# LAUNCHXL-F28377S_4.net
KiCad netlist of a schematic drawn in Altium Designer
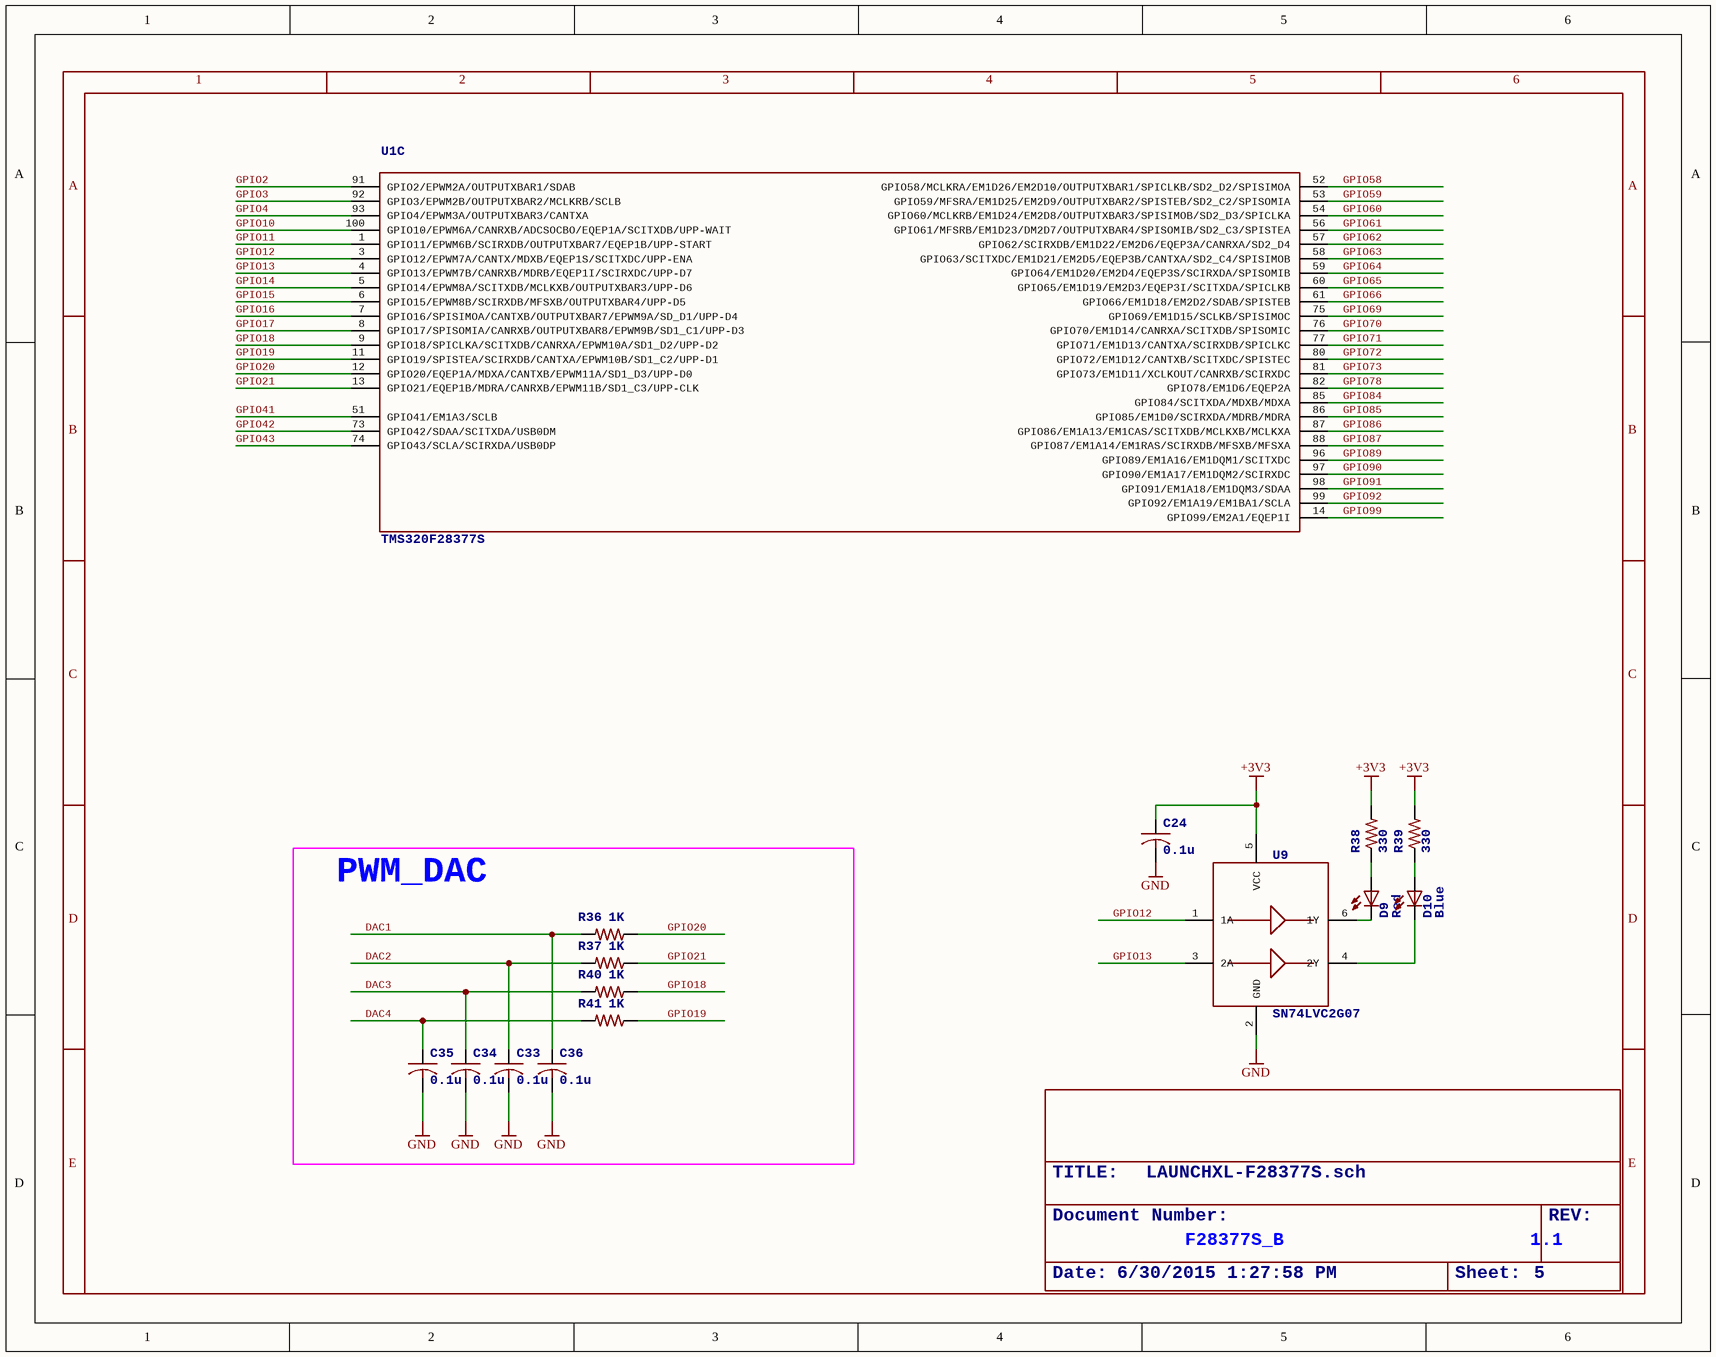
[diagram p0: LAUNCHXL-F28377S_4.SchDoc]

(export (version "E")
  (design (tool "Eeschema 10.0.6"))
  (components
    (comp (ref "C24")
      (value "0.1u")
      (footprint "C0402")
      (description "<B>CAPACITOR</B>, American symbol")
      (libsource (lib "rcl") (part "C-USC0402"))
    )
    (comp (ref "C33")
      (value "0.1u")
      (footprint "C0402")
      (description "<B>CAPACITOR</B>, American symbol")
      (libsource (lib "rcl") (part "C-USC0402"))
    )
    (comp (ref "C34")
      (value "0.1u")
      (footprint "C0402")
      (description "<B>CAPACITOR</B>, American symbol")
      (libsource (lib "rcl") (part "C-USC0402"))
    )
    (comp (ref "C35")
      (value "0.1u")
      (footprint "C0402")
      (description "<B>CAPACITOR</B>, American symbol")
      (libsource (lib "rcl") (part "C-USC0402"))
    )
    (comp (ref "C36")
      (value "0.1u")
      (footprint "C0402")
      (description "<B>CAPACITOR</B>, American symbol")
      (libsource (lib "rcl") (part "C-USC0402"))
    )
    (comp (ref "D9")
      (value "Red")
      (footprint "CHIP-LED0603")
      (libsource (lib "led") (part "LEDCHIP-LED0603"))
    )
    (comp (ref "D10")
      (value "Blue")
      (footprint "CHIP-LED0603")
      (libsource (lib "led") (part "LEDCHIP-LED0603"))
    )
    (comp (ref "R36")
      (value "1K")
      (footprint "R0402")
      (description "<B>RESISTOR</B>, American symbol")
      (libsource (lib "rcl") (part "R-US_R0402"))
    )
    (comp (ref "R37")
      (value "1K")
      (footprint "R0402")
      (description "<B>RESISTOR</B>, American symbol")
      (libsource (lib "rcl") (part "R-US_R0402"))
    )
    (comp (ref "R38")
      (value "330")
      (footprint "R0402")
      (description "<B>RESISTOR</B>, American symbol")
      (libsource (lib "rcl") (part "R-US_R0402"))
    )
    (comp (ref "R39")
      (value "330")
      (footprint "R0402")
      (description "<B>RESISTOR</B>, American symbol")
      (libsource (lib "rcl") (part "R-US_R0402"))
    )
    (comp (ref "R40")
      (value "1K")
      (footprint "R0402")
      (description "<B>RESISTOR</B>, American symbol")
      (libsource (lib "rcl") (part "R-US_R0402"))
    )
    (comp (ref "R41")
      (value "1K")
      (footprint "R0402")
      (description "<B>RESISTOR</B>, American symbol")
      (libsource (lib "rcl") (part "R-US_R0402"))
    )
    (comp (ref "U1")
      (value "TMS320F28377S")
      (footprint "PQFP100_THERMAL")
      (libsource (lib "LAUNCHXL-F28377S") (part "TMS320F28377S"))
    )
    (comp (ref "U9")
      (value "SN74LVC2G07")
      (footprint "SOT23-6-DBV")
      (libsource (lib "texas") (part "SN74LVC2G07"))
    )
  )
  (nets
    (net (code "1") (name "+3V3") (class "Default")
      (node (ref "C24") (pin "1") (pinfunction "1_1") (pintype "passive"))
      (node (ref "R38") (pin "2") (pinfunction "2_2") (pintype "passive"))
      (node (ref "R39") (pin "2") (pinfunction "2_2") (pintype "passive"))
      (node (ref "U9") (pin "5") (pinfunction "VCC_5") (pintype "passive"))
    )
    (net (code "2") (name "/DAC1") (class "Default")
      (node (ref "C36") (pin "1") (pinfunction "1_1") (pintype "passive"))
      (node (ref "R36") (pin "2") (pinfunction "2_2") (pintype "passive"))
    )
    (net (code "3") (name "/DAC2") (class "Default")
      (node (ref "C33") (pin "1") (pinfunction "1_1") (pintype "passive"))
      (node (ref "R37") (pin "2") (pinfunction "2_2") (pintype "passive"))
    )
    (net (code "4") (name "/DAC3") (class "Default")
      (node (ref "C34") (pin "1") (pinfunction "1_1") (pintype "passive"))
      (node (ref "R40") (pin "2") (pinfunction "2_2") (pintype "passive"))
    )
    (net (code "5") (name "/DAC4") (class "Default")
      (node (ref "C35") (pin "1") (pinfunction "1_1") (pintype "passive"))
      (node (ref "R41") (pin "2") (pinfunction "2_2") (pintype "passive"))
    )
    (net (code "6") (name "/GPIO2") (class "Default")
      (node (ref "U1") (pin "91") (pinfunction "GPIO2/EPWM2A/OUTPUTXBAR1/SDAB_91") (pintype "passive"))
    )
    (net (code "7") (name "/GPIO3") (class "Default")
      (node (ref "U1") (pin "92") (pinfunction "GPIO3/EPWM2B/OUTPUTXBAR2/MCLKRB/SCLB_92") (pintype "passive"))
    )
    (net (code "8") (name "/GPIO4") (class "Default")
      (node (ref "U1") (pin "93") (pinfunction "GPIO4/EPWM3A/OUTPUTXBAR3/CANTXA_93") (pintype "passive"))
    )
    (net (code "9") (name "/GPIO10") (class "Default")
      (node (ref "U1") (pin "100") (pinfunction "GPIO10/EPWM6A/CANRXB/ADCSOCBO/EQEP1A/SCITXDB/UPP-WAIT_100") (pintype "passive"))
    )
    (net (code "10") (name "/GPIO11") (class "Default")
      (node (ref "U1") (pin "1") (pinfunction "GPIO11/EPWM6B/SCIRXDB/OUTPUTXBAR7/EQEP1B/UPP-START_1") (pintype "passive"))
    )
    (net (code "11") (name "/GPIO12") (class "Default")
      (node (ref "U1") (pin "3") (pinfunction "GPIO12/EPWM7A/CANTX/MDXB/EQEP1S/SCITXDC/UPP-ENA_3") (pintype "passive"))
      (node (ref "U9") (pin "1") (pinfunction "1A_1") (pintype "passive"))
    )
    (net (code "12") (name "/GPIO13") (class "Default")
      (node (ref "U1") (pin "4") (pinfunction "GPIO13/EPWM7B/CANRXB/MDRB/EQEP1I/SCIRXDC/UPP-D7_4") (pintype "passive"))
      (node (ref "U9") (pin "3") (pinfunction "2A_3") (pintype "passive"))
    )
    (net (code "13") (name "/GPIO14") (class "Default")
      (node (ref "U1") (pin "5") (pinfunction "GPIO14/EPWM8A/SCITXDB/MCLKXB/OUTPUTXBAR3/UPP-D6_5") (pintype "passive"))
    )
    (net (code "14") (name "/GPIO15") (class "Default")
      (node (ref "U1") (pin "6") (pinfunction "GPIO15/EPWM8B/SCIRXDB/MFSXB/OUTPUTXBAR4/UPP-D5_6") (pintype "passive"))
    )
    (net (code "15") (name "/GPIO16") (class "Default")
      (node (ref "U1") (pin "7") (pinfunction "GPIO16/SPISIMOA/CANTXB/OUTPUTXBAR7/EPWM9A/SD_D1/UPP-D4_7") (pintype "passive"))
    )
    (net (code "16") (name "/GPIO17") (class "Default")
      (node (ref "U1") (pin "8") (pinfunction "GPIO17/SPISOMIA/CANRXB/OUTPUTXBAR8/EPWM9B/SD1_C1/UPP-D3_8") (pintype "passive"))
    )
    (net (code "17") (name "/GPIO18") (class "Default")
      (node (ref "R40") (pin "1") (pinfunction "1_1") (pintype "passive"))
      (node (ref "U1") (pin "9") (pinfunction "GPIO18/SPICLKA/SCITXDB/CANRXA/EPWM10A/SD1_D2/UPP-D2_9") (pintype "passive"))
    )
    (net (code "18") (name "/GPIO19") (class "Default")
      (node (ref "R41") (pin "1") (pinfunction "1_1") (pintype "passive"))
      (node (ref "U1") (pin "11") (pinfunction "GPIO19/SPISTEA/SCIRXDB/CANTXA/EPWM10B/SD1_C2/UPP-D1_11") (pintype "passive"))
    )
    (net (code "19") (name "/GPIO20") (class "Default")
      (node (ref "R36") (pin "1") (pinfunction "1_1") (pintype "passive"))
      (node (ref "U1") (pin "12") (pinfunction "GPIO20/EQEP1A/MDXA/CANTXB/EPWM11A/SD1_D3/UPP-D0_12") (pintype "passive"))
    )
    (net (code "20") (name "/GPIO21") (class "Default")
      (node (ref "R37") (pin "1") (pinfunction "1_1") (pintype "passive"))
      (node (ref "U1") (pin "13") (pinfunction "GPIO21/EQEP1B/MDRA/CANRXB/EPWM11B/SD1_C3/UPP-CLK_13") (pintype "passive"))
    )
    (net (code "21") (name "/GPIO41") (class "Default")
      (node (ref "U1") (pin "51") (pinfunction "GPIO41/EM1A3/SCLB_51") (pintype "passive"))
    )
    (net (code "22") (name "/GPIO42") (class "Default")
      (node (ref "U1") (pin "73") (pinfunction "GPIO42/SDAA/SCITXDA/USB0DM_73") (pintype "passive"))
    )
    (net (code "23") (name "/GPIO43") (class "Default")
      (node (ref "U1") (pin "74") (pinfunction "GPIO43/SCLA/SCIRXDA/USB0DP_74") (pintype "passive"))
    )
    (net (code "24") (name "/GPIO58") (class "Default")
      (node (ref "U1") (pin "52") (pinfunction "GPIO58/MCLKRA/EM1D26/EM2D10/OUTPUTXBAR1/SPICLKB/SD2_D2/SPISIMOA_52") (pintype "passive"))
    )
    (net (code "25") (name "/GPIO59") (class "Default")
      (node (ref "U1") (pin "53") (pinfunction "GPIO59/MFSRA/EM1D25/EM2D9/OUTPUTXBAR2/SPISTEB/SD2_C2/SPISOMIA_53") (pintype "passive"))
    )
    (net (code "26") (name "/GPIO60") (class "Default")
      (node (ref "U1") (pin "54") (pinfunction "GPIO60/MCLKRB/EM1D24/EM2D8/OUTPUTXBAR3/SPISIMOB/SD2_D3/SPICLKA_54") (pintype "passive"))
    )
    (net (code "27") (name "/GPIO61") (class "Default")
      (node (ref "U1") (pin "56") (pinfunction "GPIO61/MFSRB/EM1D23/DM2D7/OUTPUTXBAR4/SPISOMIB/SD2_C3/SPISTEA_56") (pintype "passive"))
    )
    (net (code "28") (name "/GPIO62") (class "Default")
      (node (ref "U1") (pin "57") (pinfunction "GPIO62/SCIRXDB/EM1D22/EM2D6/EQEP3A/CANRXA/SD2_D4_57") (pintype "passive"))
    )
    (net (code "29") (name "/GPIO63") (class "Default")
      (node (ref "U1") (pin "58") (pinfunction "GPIO63/SCITXDC/EM1D21/EM2D5/EQEP3B/CANTXA/SD2_C4/SPISIMOB_58") (pintype "passive"))
    )
    (net (code "30") (name "/GPIO64") (class "Default")
      (node (ref "U1") (pin "59") (pinfunction "GPIO64/EM1D20/EM2D4/EQEP3S/SCIRXDA/SPISOMIB_59") (pintype "passive"))
    )
    (net (code "31") (name "/GPIO65") (class "Default")
      (node (ref "U1") (pin "60") (pinfunction "GPIO65/EM1D19/EM2D3/EQEP3I/SCITXDA/SPICLKB_60") (pintype "passive"))
    )
    (net (code "32") (name "/GPIO66") (class "Default")
      (node (ref "U1") (pin "61") (pinfunction "GPIO66/EM1D18/EM2D2/SDAB/SPISTEB_61") (pintype "passive"))
    )
    (net (code "33") (name "/GPIO69") (class "Default")
      (node (ref "U1") (pin "75") (pinfunction "GPIO69/EM1D15/SCLKB/SPISIMOC_75") (pintype "passive"))
    )
    (net (code "34") (name "/GPIO70") (class "Default")
      (node (ref "U1") (pin "76") (pinfunction "GPIO70/EM1D14/CANRXA/SCITXDB/SPISOMIC_76") (pintype "passive"))
    )
    (net (code "35") (name "/GPIO71") (class "Default")
      (node (ref "U1") (pin "77") (pinfunction "GPIO71/EM1D13/CANTXA/SCIRXDB/SPICLKC_77") (pintype "passive"))
    )
    (net (code "36") (name "/GPIO72") (class "Default")
      (node (ref "U1") (pin "80") (pinfunction "GPIO72/EM1D12/CANTXB/SCITXDC/SPISTEC_80") (pintype "passive"))
    )
    (net (code "37") (name "/GPIO73") (class "Default")
      (node (ref "U1") (pin "81") (pinfunction "GPIO73/EM1D11/XCLKOUT/CANRXB/SCIRXDC_81") (pintype "passive"))
    )
    (net (code "38") (name "/GPIO78") (class "Default")
      (node (ref "U1") (pin "82") (pinfunction "GPIO78/EM1D6/EQEP2A_82") (pintype "passive"))
    )
    (net (code "39") (name "/GPIO84") (class "Default")
      (node (ref "U1") (pin "85") (pinfunction "GPIO84/SCITXDA/MDXB/MDXA_85") (pintype "passive"))
    )
    (net (code "40") (name "/GPIO85") (class "Default")
      (node (ref "U1") (pin "86") (pinfunction "GPIO85/EM1D0/SCIRXDA/MDRB/MDRA_86") (pintype "passive"))
    )
    (net (code "41") (name "/GPIO86") (class "Default")
      (node (ref "U1") (pin "87") (pinfunction "GPIO86/EM1A13/EM1CAS/SCITXDB/MCLKXB/MCLKXA_87") (pintype "passive"))
    )
    (net (code "42") (name "/GPIO87") (class "Default")
      (node (ref "U1") (pin "88") (pinfunction "GPIO87/EM1A14/EM1RAS/SCIRXDB/MFSXB/MFSXA_88") (pintype "passive"))
    )
    (net (code "43") (name "/GPIO89") (class "Default")
      (node (ref "U1") (pin "96") (pinfunction "GPIO89/EM1A16/EM1DQM1/SCITXDC_96") (pintype "passive"))
    )
    (net (code "44") (name "/GPIO90") (class "Default")
      (node (ref "U1") (pin "97") (pinfunction "GPIO90/EM1A17/EM1DQM2/SCIRXDC_97") (pintype "passive"))
    )
    (net (code "45") (name "/GPIO91") (class "Default")
      (node (ref "U1") (pin "98") (pinfunction "GPIO91/EM1A18/EM1DQM3/SDAA_98") (pintype "passive"))
    )
    (net (code "46") (name "/GPIO92") (class "Default")
      (node (ref "U1") (pin "99") (pinfunction "GPIO92/EM1A19/EM1BA1/SCLA_99") (pintype "passive"))
    )
    (net (code "47") (name "/GPIO99") (class "Default")
      (node (ref "U1") (pin "14") (pinfunction "GPIO99/EM2A1/EQEP1I_14") (pintype "passive"))
    )
    (net (code "48") (name "GND") (class "Default")
      (node (ref "C24") (pin "2") (pinfunction "2_2") (pintype "passive"))
      (node (ref "C33") (pin "2") (pinfunction "2_2") (pintype "passive"))
      (node (ref "C34") (pin "2") (pinfunction "2_2") (pintype "passive"))
      (node (ref "C35") (pin "2") (pinfunction "2_2") (pintype "passive"))
      (node (ref "C36") (pin "2") (pinfunction "2_2") (pintype "passive"))
      (node (ref "U9") (pin "2") (pinfunction "GND_2") (pintype "passive"))
    )
    (net (code "49") (name "Net-(D9-PadA)") (class "Default")
      (node (ref "D9") (pin "A") (pinfunction "A_A") (pintype "passive"))
      (node (ref "R38") (pin "1") (pinfunction "1_1") (pintype "passive"))
    )
    (net (code "50") (name "Net-(D10-PadA)") (class "Default")
      (node (ref "D10") (pin "A") (pinfunction "A_A") (pintype "passive"))
      (node (ref "R39") (pin "1") (pinfunction "1_1") (pintype "passive"))
    )
    (net (code "51") (name "Net-(U9-1Y)") (class "Default")
      (node (ref "D9") (pin "C") (pinfunction "C_C") (pintype "passive"))
      (node (ref "U9") (pin "6") (pinfunction "1Y_6") (pintype "passive"))
    )
    (net (code "52") (name "Net-(U9-2Y)") (class "Default")
      (node (ref "D10") (pin "C") (pinfunction "C_C") (pintype "passive"))
      (node (ref "U9") (pin "4") (pinfunction "2Y_4") (pintype "passive"))
    )
  )
)
